# main.net
KiCad netlist of a schematic drawn in Altium Designer
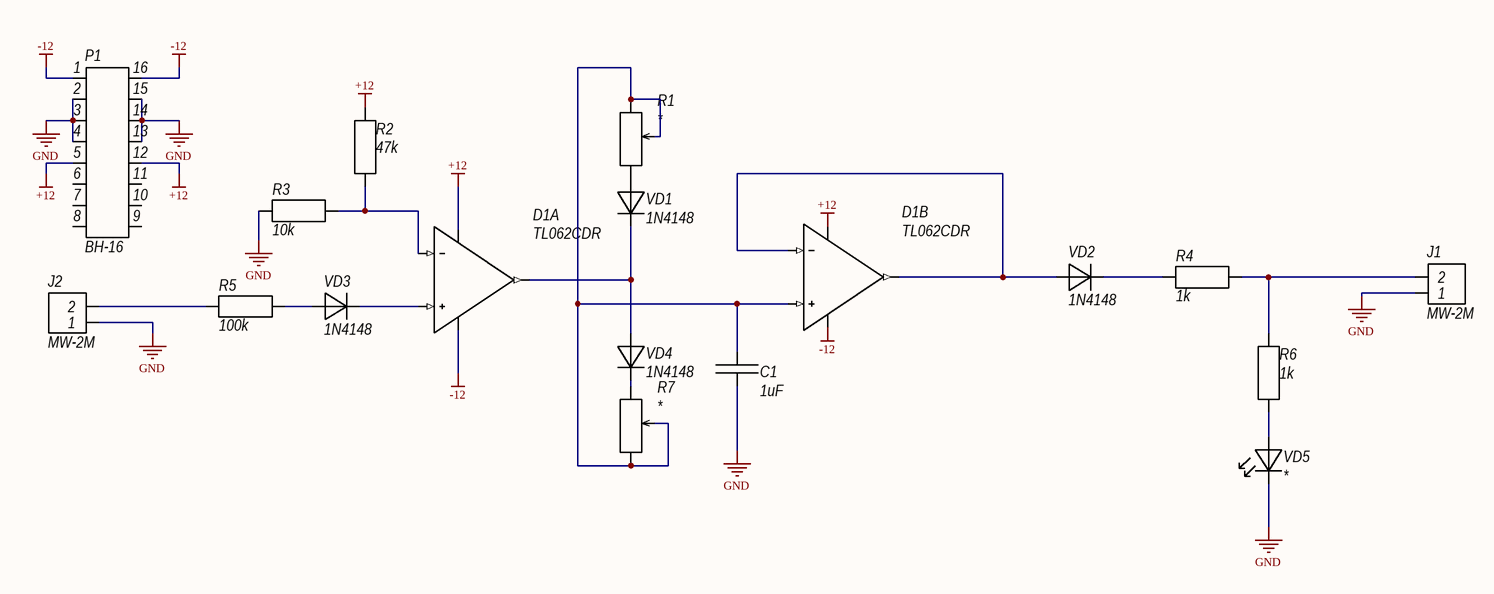
[diagram p0: main.SchDoc]

(export (version "E")
  (design (tool "Eeschema 10.0.6"))
  (components
    (comp (ref "C1") (value "1uF") (footprint "CAP DISK 5mm") (libsource (lib "Schlib1") (part "Capacitor")))
    (comp (ref "D1")
      (value "TL062CDR")
      (footprint "DIP-8")
      (fields (field (name "MANUFACTURER") "Texas Instruments"))
      (libsource (lib "Schlib1") (part "TL062"))
    )
    (comp (ref "J1") (value "MW-2M") (footprint "MW-2M") (libsource (lib "Schlib1") (part "MW-2M")))
    (comp (ref "J2") (value "MW-2M") (footprint "MW-2M") (libsource (lib "Schlib1") (part "MW-2M")))
    (comp (ref "P1") (value "BH-16") (footprint "BH-16") (libsource (lib "Schlib1") (part "BH-16")))
    (comp (ref "R1") (value "*") (footprint "WF-3") (libsource (lib "Schlib1") (part "Potentiometr")))
    (comp (ref "R2") (value "47k") (footprint "R1206") (libsource (lib "Schlib1") (part "Resistor")))
    (comp (ref "R3") (value "10k") (footprint "R1206") (libsource (lib "") (part "Resistor_1")))
    (comp (ref "R4") (value "1k") (footprint "R1206") (libsource (lib "") (part "Resistor_1")))
    (comp (ref "R5") (value "100k") (footprint "R1206") (libsource (lib "") (part "Resistor_1")))
    (comp (ref "R6") (value "1k") (footprint "R1206") (libsource (lib "Schlib1") (part "Resistor")))
    (comp (ref "R7") (value "*") (footprint "potentiometr hor") (libsource (lib "") (part "Potentiometr_1")))
    (comp (ref "VD1")
      (value "1N4148")
      (footprint "SOD-123")
      (description "DIODE GEN PURP 75V 150MA")
      (fields (field (name "MANUFACTURER") "Vishay Semiconductor Diodes Division"))
      (libsource (lib "Schlib1") (part "1N4148W-E3-18"))
    )
    (comp (ref "VD2")
      (value "1N4148")
      (footprint "SOD-123")
      (description "DIODE GEN PURP 75V 150MA")
      (fields (field (name "MANUFACTURER") "Vishay Semiconductor Diodes Division"))
      (libsource (lib "Schlib1") (part "1N4148W-E3-18"))
    )
    (comp (ref "VD3")
      (value "1N4148")
      (footprint "SOD-123")
      (description "DIODE GEN PURP 75V 150MA")
      (fields (field (name "MANUFACTURER") "Vishay Semiconductor Diodes Division"))
      (libsource (lib "Schlib1") (part "1N4148W-E3-18"))
    )
    (comp (ref "VD4")
      (value "1N4148")
      (footprint "SOD-123")
      (description "DIODE GEN PURP 75V 150MA")
      (fields (field (name "MANUFACTURER") "Vishay Semiconductor Diodes Division"))
      (libsource (lib "Schlib1") (part "1N4148W-E3-18"))
    )
    (comp (ref "VD5") (value "*") (footprint "LED-5mm") (libsource (lib "Schlib1") (part "LED")))
  )
  (nets
    (net (code "1") (name "+12") (class "Default")
      (node (ref "D1") (pin "8") (pinfunction "Vcc+_8") (pintype "power_in"))
      (node (ref "P1") (pin "12") (pinfunction "12_12") (pintype "passive"))
      (node (ref "P1") (pin "5") (pinfunction "5_5") (pintype "passive"))
      (node (ref "R2") (pin "2") (pintype "passive"))
    )
    (net (code "2") (name "-12") (class "Default")
      (node (ref "D1") (pin "4") (pinfunction "Vcc-_4") (pintype "power_in"))
      (node (ref "P1") (pin "1") (pinfunction "1_1") (pintype "passive"))
      (node (ref "P1") (pin "16") (pinfunction "16_16") (pintype "passive"))
    )
    (net (code "3") (name "GND") (class "Default")
      (node (ref "C1") (pin "1") (pintype "passive"))
      (node (ref "J1") (pin "1") (pinfunction "1_1") (pintype "passive"))
      (node (ref "J2") (pin "1") (pinfunction "1_1") (pintype "passive"))
      (node (ref "P1") (pin "13") (pinfunction "13_13") (pintype "passive"))
      (node (ref "P1") (pin "14") (pinfunction "14_14") (pintype "passive"))
      (node (ref "P1") (pin "15") (pinfunction "15_15") (pintype "passive"))
      (node (ref "P1") (pin "2") (pinfunction "2_2") (pintype "passive"))
      (node (ref "P1") (pin "3") (pinfunction "3_3") (pintype "passive"))
      (node (ref "P1") (pin "4") (pinfunction "4_4") (pintype "passive"))
      (node (ref "R3") (pin "1") (pintype "passive"))
      (node (ref "VD5") (pin "2") (pintype "passive"))
    )
    (net (code "4") (name "Net-(D1A-1IN+)") (class "Default")
      (node (ref "D1") (pin "3") (pinfunction "1IN+_3") (pintype "input"))
      (node (ref "VD3") (pin "2") (pintype "passive"))
    )
    (net (code "5") (name "Net-(D1A-1IN-)") (class "Default")
      (node (ref "D1") (pin "2") (pinfunction "1IN-_2") (pintype "input"))
      (node (ref "R2") (pin "1") (pintype "passive"))
      (node (ref "R3") (pin "2") (pintype "passive"))
    )
    (net (code "6") (name "Net-(D1A-1OUT)") (class "Default")
      (node (ref "D1") (pin "1") (pinfunction "1OUT_1") (pintype "output"))
      (node (ref "VD1") (pin "2") (pintype "passive"))
      (node (ref "VD4") (pin "1") (pintype "passive"))
    )
    (net (code "7") (name "Net-(D1B-2IN-)") (class "Default")
      (node (ref "D1") (pin "6") (pinfunction "2IN-_6") (pintype "input"))
      (node (ref "D1") (pin "7") (pinfunction "2OUT_7") (pintype "output"))
      (node (ref "VD2") (pin "1") (pintype "passive"))
    )
    (net (code "8") (name "Net-(D1B-21IN+)") (class "Default")
      (node (ref "C1") (pin "2") (pintype "passive"))
      (node (ref "D1") (pin "5") (pinfunction "21IN+_5") (pintype "input"))
      (node (ref "R1") (pin "1") (pintype "passive"))
      (node (ref "R1") (pin "2") (pintype "passive"))
      (node (ref "R7") (pin "2") (pintype "passive"))
      (node (ref "R7") (pin "3") (pintype "passive"))
    )
    (net (code "9") (name "Net-(J1-Pad2)") (class "Default")
      (node (ref "J1") (pin "2") (pinfunction "2_2") (pintype "passive"))
      (node (ref "R4") (pin "2") (pintype "passive"))
      (node (ref "R6") (pin "2") (pintype "passive"))
    )
    (net (code "10") (name "Net-(J2-Pad2)") (class "Default")
      (node (ref "J2") (pin "2") (pinfunction "2_2") (pintype "passive"))
      (node (ref "R5") (pin "1") (pintype "passive"))
    )
    (net (code "11") (name "Net-(R1-Pad3)") (class "Default")
      (node (ref "R1") (pin "3") (pintype "passive"))
      (node (ref "VD1") (pin "1") (pintype "passive"))
    )
    (net (code "12") (name "Net-(R4-Pad1)") (class "Default")
      (node (ref "R4") (pin "1") (pintype "passive"))
      (node (ref "VD2") (pin "2") (pintype "passive"))
    )
    (net (code "13") (name "Net-(R5-Pad2)") (class "Default")
      (node (ref "R5") (pin "2") (pintype "passive"))
      (node (ref "VD3") (pin "1") (pintype "passive"))
    )
    (net (code "14") (name "Net-(R6-Pad1)") (class "Default")
      (node (ref "R6") (pin "1") (pintype "passive"))
      (node (ref "VD5") (pin "1") (pintype "passive"))
    )
    (net (code "15") (name "Net-(R7-Pad1)") (class "Default")
      (node (ref "R7") (pin "1") (pintype "passive"))
      (node (ref "VD4") (pin "2") (pintype "passive"))
    )
    (net (code "16") (name "unconnected-(P1-Pad6)") (class "Default")
      (node (ref "P1") (pin "6") (pinfunction "6_6") (pintype "passive"))
    )
    (net (code "17") (name "unconnected-(P1-Pad7)") (class "Default")
      (node (ref "P1") (pin "7") (pinfunction "7_7") (pintype "passive"))
    )
    (net (code "18") (name "unconnected-(P1-Pad8)") (class "Default")
      (node (ref "P1") (pin "8") (pinfunction "8_8") (pintype "passive"))
    )
    (net (code "19") (name "unconnected-(P1-Pad9)") (class "Default")
      (node (ref "P1") (pin "9") (pinfunction "9_9") (pintype "passive"))
    )
    (net (code "20") (name "unconnected-(P1-Pad10)") (class "Default")
      (node (ref "P1") (pin "10") (pinfunction "10_10") (pintype "passive"))
    )
    (net (code "21") (name "unconnected-(P1-Pad11)") (class "Default")
      (node (ref "P1") (pin "11") (pinfunction "11_11") (pintype "passive"))
    )
  )
)
